# Connector-Harness.net
KiCad netlist of a schematic drawn in Altium Designer
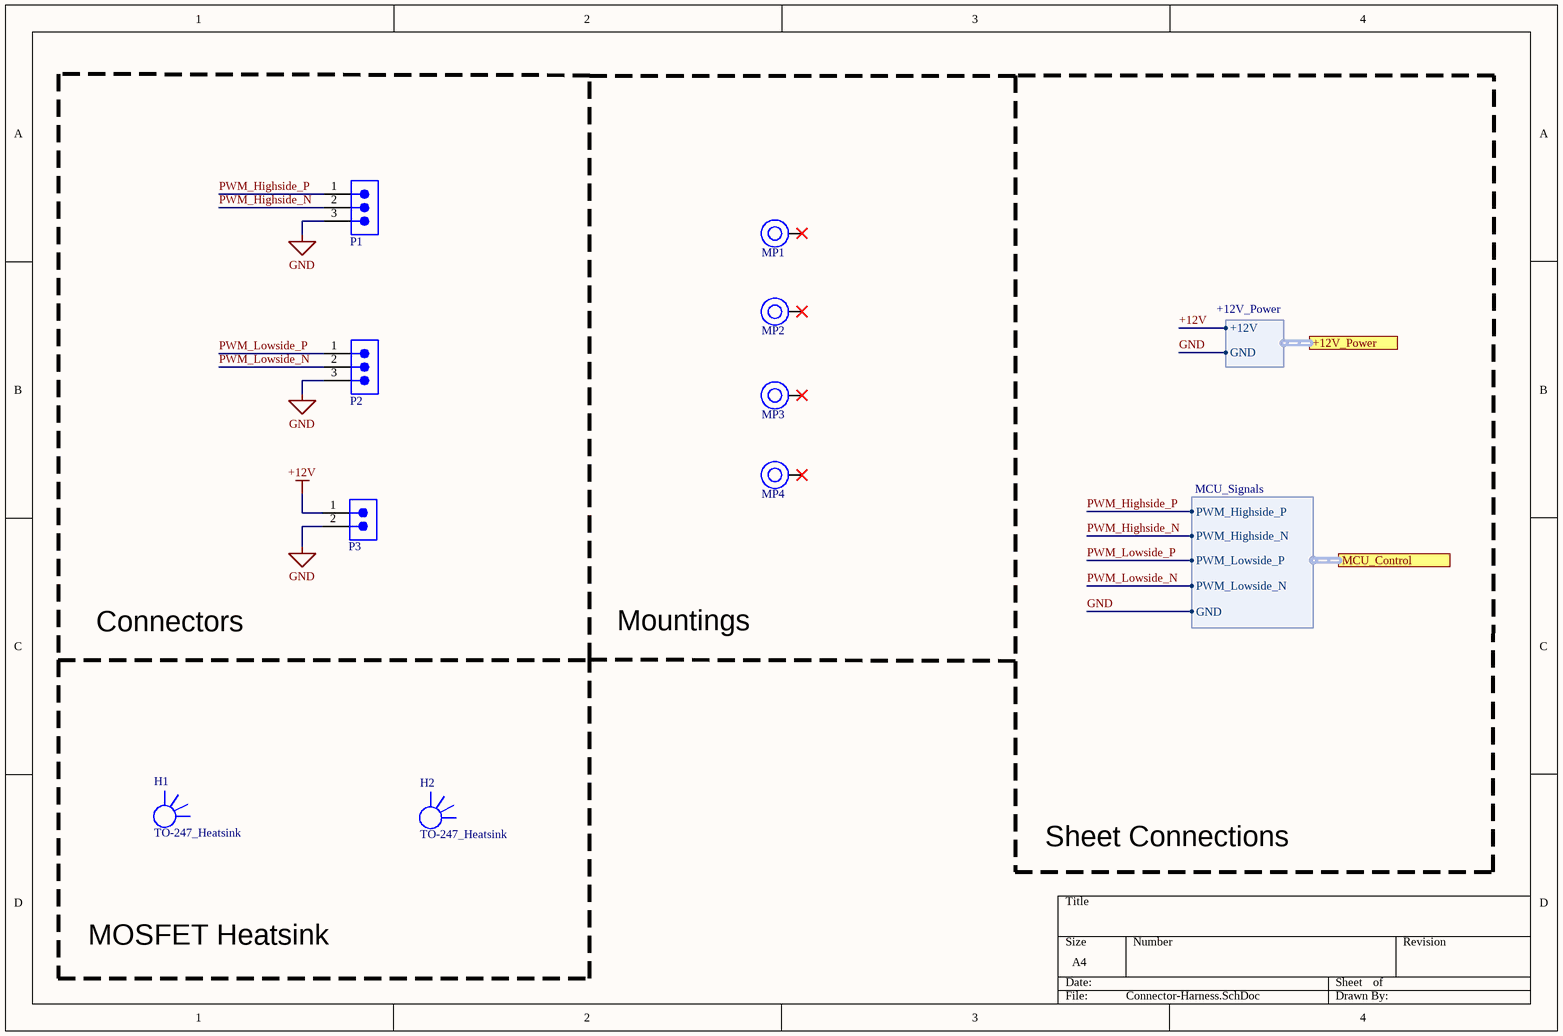
[diagram p0: Connector-Harness.SchDoc]

(export (version "E")
  (design (tool "Eeschema 10.0.6"))
  (components
    (comp (ref "H1")
      (value "TO-247_Heatsink")
      (footprint "Heatsink")
      (libsource (lib "Schlib1") (part "TO-247_Heatsink"))
    )
    (comp (ref "H2")
      (value "TO-247_Heatsink")
      (footprint "Heatsink")
      (libsource (lib "Schlib1") (part "TO-247_Heatsink"))
    )
    (comp (ref "MP1")
      (value "Hole 3.3mm x 9mm")
      (footprint "78614090960")
      (description "WA-SMSA SMT Spacer Studs Automotive, OD 6mm, ID 4.2mm, Hole 3.3mm x 9mm")
      (fields
        (field (name "MANUFACTURER PART NUMBER") "78614090960")
        (field (name "MANUFACTURER") "Wurth Elektronik")
      )
      (libsource (lib "WE - Electromechanical Components") (part "Spacer"))
    )
    (comp (ref "MP2")
      (value "Hole 3.3mm x 9mm")
      (footprint "78614090960")
      (description "WA-SMSA SMT Spacer Studs Automotive, OD 6mm, ID 4.2mm, Hole 3.3mm x 9mm")
      (fields
        (field (name "MANUFACTURER PART NUMBER") "78614090960")
        (field (name "MANUFACTURER") "Wurth Elektronik")
      )
      (libsource (lib "WE - Electromechanical Components") (part "Spacer"))
    )
    (comp (ref "MP3")
      (value "Hole 3.3mm x 9mm")
      (footprint "78614090960")
      (description "WA-SMSA SMT Spacer Studs Automotive, OD 6mm, ID 4.2mm, Hole 3.3mm x 9mm")
      (fields
        (field (name "MANUFACTURER PART NUMBER") "78614090960")
        (field (name "MANUFACTURER") "Wurth Elektronik")
      )
      (libsource (lib "WE - Electromechanical Components") (part "Spacer"))
    )
    (comp (ref "MP4")
      (value "Hole 3.3mm x 9mm")
      (footprint "78614090960")
      (description "WA-SMSA SMT Spacer Studs Automotive, OD 6mm, ID 4.2mm, Hole 3.3mm x 9mm")
      (fields
        (field (name "MANUFACTURER PART NUMBER") "78614090960")
        (field (name "MANUFACTURER") "Wurth Elektronik")
      )
      (libsource (lib "WE - Electromechanical Components") (part "Spacer"))
    )
    (comp (ref "P1")
      (value "61900311121")
      (footprint "61900311121")
      (description "WR-WTB THT Male Vertical Locking Header, pitch 2.54mm, 3pins")
      (fields (field (name "MANUFACTURER") "Wurth Elektronik"))
      (libsource (lib "WE - Electromechanical Components") (part "Header_Male_1R_03P"))
    )
    (comp (ref "P2")
      (value "61900311121")
      (footprint "61900311121")
      (description "WR-WTB THT Male Vertical Locking Header, pitch 2.54mm, 3pins")
      (fields (field (name "MANUFACTURER") "Wurth Elektronik"))
      (libsource (lib "WE - Electromechanical Components") (part "Header_Male_1R_03P"))
    )
    (comp (ref "P3")
      (value "61900211121")
      (footprint "61900211121")
      (description "WR-WTB THT Male Vertical Locking Header, pitch 2.54mm, 2pins")
      (fields (field (name "MANUFACTURER") "Wurth Elektronik"))
      (libsource (lib "WE - Electromechanical Components") (part "Header_Male_1R_02P"))
    )
  )
  (nets
    (net (code "3") (name "+12V") (class "Default")
      (node (ref "P3") (pin "1") (pinfunction "1_1") (pintype "passive"))
    )
    (net (code "4") (name "/PWM_Highside_N") (class "Default")
      (node (ref "P1") (pin "2") (pinfunction "2_2") (pintype "passive"))
    )
    (net (code "5") (name "/PWM_Highside_P") (class "Default")
      (node (ref "P1") (pin "1") (pinfunction "1_1") (pintype "passive"))
    )
    (net (code "6") (name "/PWM_Lowside_N") (class "Default")
      (node (ref "P2") (pin "2") (pinfunction "2_2") (pintype "passive"))
    )
    (net (code "7") (name "/PWM_Lowside_P") (class "Default")
      (node (ref "P2") (pin "1") (pinfunction "1_1") (pintype "passive"))
    )
    (net (code "10") (name "GND") (class "Default")
      (node (ref "P1") (pin "3") (pinfunction "3_3") (pintype "passive"))
      (node (ref "P2") (pin "3") (pinfunction "3_3") (pintype "passive"))
      (node (ref "P3") (pin "2") (pinfunction "2_2") (pintype "passive"))
    )
    (net (code "11") (name "unconnected-(MP1-Pad1)") (class "Default")
      (node (ref "MP1") (pin "1") (pinfunction "1_1") (pintype "passive+no_connect"))
    )
    (net (code "12") (name "unconnected-(MP2-Pad1)") (class "Default")
      (node (ref "MP2") (pin "1") (pinfunction "1_1") (pintype "passive+no_connect"))
    )
    (net (code "13") (name "unconnected-(MP3-Pad1)") (class "Default")
      (node (ref "MP3") (pin "1") (pinfunction "1_1") (pintype "passive+no_connect"))
    )
    (net (code "14") (name "unconnected-(MP4-Pad1)") (class "Default")
      (node (ref "MP4") (pin "1") (pinfunction "1_1") (pintype "passive+no_connect"))
    )
  )
)
